# LCD1602_Driver.net
KiCad netlist of a schematic drawn in Altium Designer
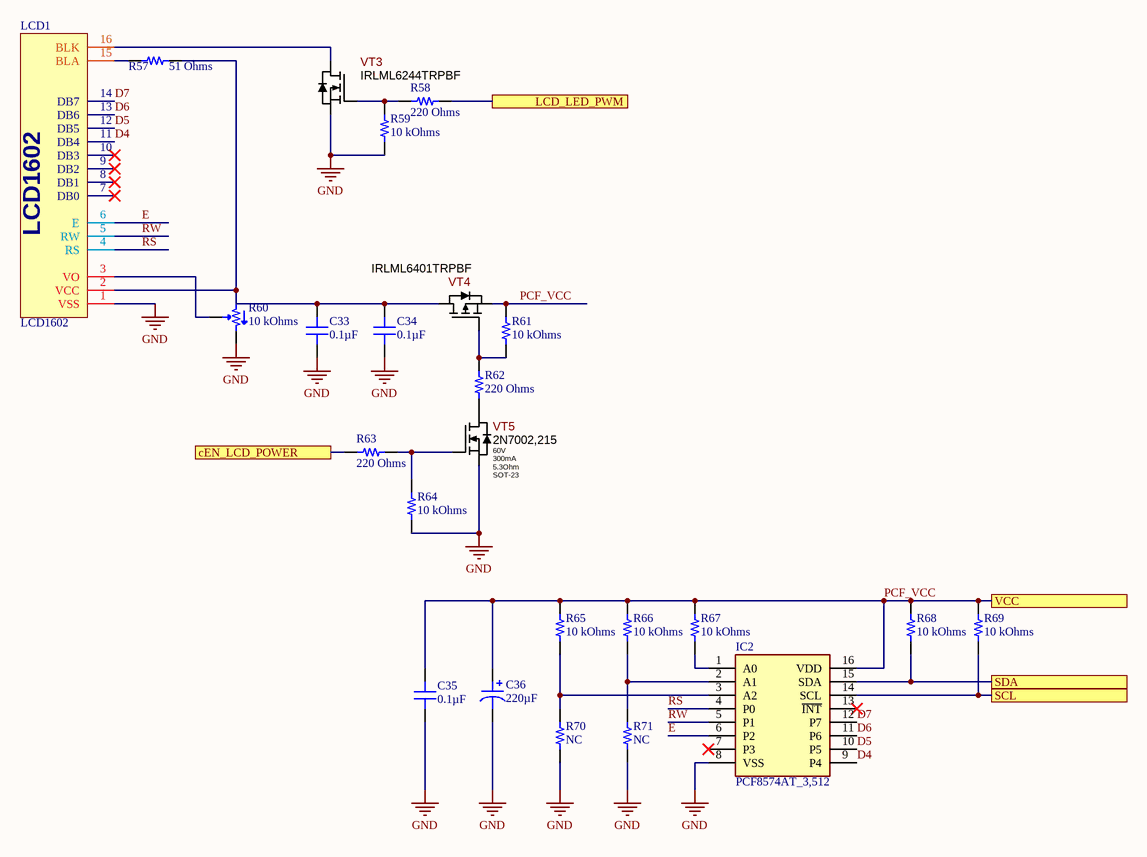
[diagram p0: LCD1602_Driver.SchDoc]

(export (version "E")
  (design (tool "Eeschema 10.0.6"))
  (components
    (comp (ref "C33")
      (value "0.1µF")
      (footprint "CAP 0805_2012")
      (description "CAP CER 0.1UF 50V X7R 0805")
      (fields (field (name "PART NUMBER") "CC0805MRX7R9BB104") (field (name "MANUFACTURER") "Yageo"))
      (libsource (lib "Celestial Altium Library - altium_library") (part "Capacitor"))
    )
    (comp (ref "C34")
      (value "0.1µF")
      (footprint "CAP 0805_2012")
      (description "CAP CER 0.1UF 50V X7R 0805")
      (fields (field (name "PART NUMBER") "CC0805MRX7R9BB104") (field (name "MANUFACTURER") "Yageo"))
      (libsource (lib "Celestial Altium Library - altium_library") (part "Capacitor"))
    )
    (comp (ref "C35")
      (value "0.1µF")
      (footprint "CAP 0805_2012")
      (description "CAP CER 0.1UF 50V X7R 0805")
      (fields (field (name "PART NUMBER") "CC0805MRX7R9BB104") (field (name "MANUFACTURER") "Yageo"))
      (libsource (lib "Celestial Altium Library - altium_library") (part "Capacitor"))
    )
    (comp (ref "C36")
      (value "220µF")
      (footprint "CAP ALSMD POLY 5.3MM H6.0MM")
      (description "CAP ALUM POLY 220UF 20% 6.3V SMD")
      (fields
        (field (name "PART NUMBER") "6SVPE220MW")
        (field (name "MANUFACTURER") "Panasonic Electronic Components")
      )
      (libsource (lib "Celestial Altium Library - altium_library") (part "Polarised Capacitor"))
    )
    (comp (ref "IC2")
      (value "PCF8574AT_3,512")
      (footprint "SamacSys:SOIC127P1032X265-16N")
      (description "Integrated Circuit")
      (fields
        (field (name "MANUFACTURER_PART_NUMBER") "PCF8574AT/3,512")
        (field (name "MOUSER PART NUMBER") "771-PCF85AT3512")
      )
      (libsource (lib "*") (part "PCF8574AT_3,512"))
    )
    (comp (ref "LCD1")
      (value "LCD1602")
      (footprint "LCD1602")
      (libsource (lib "Miscellaneous LCD") (part "LCD1602"))
    )
    (comp (ref "R57")
      (value "51 Ohms")
      (footprint "RES 0805_2012")
      (description "RES SMD 51 OHM 1% 1/4W 0805")
      (fields (field (name "PART NUMBER") "CRM0805-FX-51R0ELF") (field (name "MANUFACTURER") "Bourns Inc."))
      (libsource (lib "Celestial Altium Library - altium_library") (part "Resistor"))
    )
    (comp (ref "R58")
      (value "220 Ohms")
      (footprint "RES 0805_2012")
      (description "CRGP 0805 220R 1%")
      (fields
        (field (name "PART NUMBER") "CRGP0805F220R")
        (field (name "MANUFACTURER") "TE Connectivity Passive Product")
      )
      (libsource (lib "Celestial Altium Library - altium_library") (part "Resistor"))
    )
    (comp (ref "R59")
      (value "10 kOhms")
      (footprint "RES 0805_2012")
      (description "RES 10K OHM 0.1% 1/10W 0805")
      (fields
        (field (name "PART NUMBER") "RNCS0805BKE10K0")
        (field (name "MANUFACTURER") "Stackpole Electronics Inc")
      )
      (libsource (lib "Celestial Altium Library - altium_library") (part "Resistor"))
    )
    (comp (ref "R60")
      (value "10 kOhms")
      (footprint "POT BOURNS TRIMPOT TC33")
      (description "TRIMMER 10K OHM 0.1W J LEAD TOP")
      (fields (field (name "PART NUMBER") "TC33X-2-103E") (field (name "MANUFACTURER") "Bourns Inc."))
      (libsource (lib "Celestial Altium Library - altium_library") (part "Potentiometer"))
    )
    (comp (ref "R61")
      (value "10 kOhms")
      (footprint "RES 0805_2012")
      (description "RES 10K OHM 0.1% 1/10W 0805")
      (fields
        (field (name "PART NUMBER") "RNCS0805BKE10K0")
        (field (name "MANUFACTURER") "Stackpole Electronics Inc")
      )
      (libsource (lib "Celestial Altium Library - altium_library") (part "Resistor"))
    )
    (comp (ref "R62")
      (value "220 Ohms")
      (footprint "RES 0805_2012")
      (description "CRGP 0805 220R 1%")
      (fields
        (field (name "PART NUMBER") "CRGP0805F220R")
        (field (name "MANUFACTURER") "TE Connectivity Passive Product")
      )
      (libsource (lib "Celestial Altium Library - altium_library") (part "Resistor"))
    )
    (comp (ref "R63")
      (value "220 Ohms")
      (footprint "RES 0805_2012")
      (description "CRGP 0805 220R 1%")
      (fields
        (field (name "PART NUMBER") "CRGP0805F220R")
        (field (name "MANUFACTURER") "TE Connectivity Passive Product")
      )
      (libsource (lib "Celestial Altium Library - altium_library") (part "Resistor"))
    )
    (comp (ref "R64")
      (value "10 kOhms")
      (footprint "RES 0805_2012")
      (description "RES 10K OHM 0.1% 1/10W 0805")
      (fields
        (field (name "PART NUMBER") "RNCS0805BKE10K0")
        (field (name "MANUFACTURER") "Stackpole Electronics Inc")
      )
      (libsource (lib "Celestial Altium Library - altium_library") (part "Resistor"))
    )
    (comp (ref "R65")
      (value "10 kOhms")
      (footprint "RES 0805_2012")
      (description "RES 10K OHM 0.1% 1/10W 0805")
      (fields
        (field (name "PART NUMBER") "RNCS0805BKE10K0")
        (field (name "MANUFACTURER") "Stackpole Electronics Inc")
      )
      (libsource (lib "Celestial Altium Library - altium_library") (part "Resistor"))
    )
    (comp (ref "R66")
      (value "10 kOhms")
      (footprint "RES 0805_2012")
      (description "RES 10K OHM 0.1% 1/10W 0805")
      (fields
        (field (name "PART NUMBER") "RNCS0805BKE10K0")
        (field (name "MANUFACTURER") "Stackpole Electronics Inc")
      )
      (libsource (lib "Celestial Altium Library - altium_library") (part "Resistor"))
    )
    (comp (ref "R67")
      (value "10 kOhms")
      (footprint "RES 0805_2012")
      (description "RES 10K OHM 0.1% 1/10W 0805")
      (fields
        (field (name "PART NUMBER") "RNCS0805BKE10K0")
        (field (name "MANUFACTURER") "Stackpole Electronics Inc")
      )
      (libsource (lib "Celestial Altium Library - altium_library") (part "Resistor"))
    )
    (comp (ref "R68")
      (value "10 kOhms")
      (footprint "RES 0805_2012")
      (description "RES 10K OHM 0.1% 1/10W 0805")
      (fields
        (field (name "PART NUMBER") "RNCS0805BKE10K0")
        (field (name "MANUFACTURER") "Stackpole Electronics Inc")
      )
      (libsource (lib "Celestial Altium Library - altium_library") (part "Resistor"))
    )
    (comp (ref "R69")
      (value "10 kOhms")
      (footprint "RES 0805_2012")
      (description "RES 10K OHM 0.1% 1/10W 0805")
      (fields
        (field (name "PART NUMBER") "RNCS0805BKE10K0")
        (field (name "MANUFACTURER") "Stackpole Electronics Inc")
      )
      (libsource (lib "Celestial Altium Library - altium_library") (part "Resistor"))
    )
    (comp (ref "R70")
      (value "NC")
      (footprint "RES 0805_2012")
      (description "RES 10K OHM 0.1% 1/10W 0805")
      (fields
        (field (name "PART NUMBER") "RNCS0805BKE10K0")
        (field (name "MANUFACTURER") "Stackpole Electronics Inc")
      )
      (libsource (lib "Celestial Altium Library - altium_library") (part "Resistor"))
    )
    (comp (ref "R71")
      (value "NC")
      (footprint "RES 0805_2012")
      (description "RES 10K OHM 0.1% 1/10W 0805")
      (fields
        (field (name "PART NUMBER") "RNCS0805BKE10K0")
        (field (name "MANUFACTURER") "Stackpole Electronics Inc")
      )
      (libsource (lib "Celestial Altium Library - altium_library") (part "Resistor"))
    )
    (comp (ref "VT3")
      (value "IRLML6244")
      (footprint "SOT-23_MED")
      (description "20V, 6.3A max N-Channel HEXFET MOSFET, 21mOhm @ Vgs = 4.5V")
      (fields
        (field (name "PART NUMBER") "IRLML6244TRPBF")
        (field (name "MANUFACTURER") "Infineon Technologies")
      )
      (libsource (lib "Transistors") (part "IRLML6244TRPBF"))
    )
    (comp (ref "VT4")
      (value "IRLML6401")
      (footprint "SOT-23_MED")
      (description "-12V, -4.3A max P-Channel HEXFET MOSFET, 50mOhm @ Vgs = -4.5V")
      (fields
        (field (name "PART NUMBER") "IRLML6401TRPBF")
        (field (name "MANUFACTURER") "Infineon Technologies")
      )
      (libsource (lib "Transistors") (part "IRLML6401TRPBF"))
    )
    (comp (ref "VT5")
      (value "2N7002")
      (footprint "SOT-23_MED")
      (description "60V, 300mA max N-Channel Trench MOSFET, 3.8Ohm @ Vgs = 4.5V")
      (fields
        (field (name "MANUFACTURER") "Nexperia USA Inc.")
        (field (name "PART NUMBER") "2N7002,215")
        (field (name "VDS") "60V")
        (field (name "ID") "300mA")
        (field (name "RDS") "5.3Ohm")
        (field (name "PACKAGE") "SOT-23")
      )
      (libsource (lib "Transistors") (part "2N7002,215"))
    )
  )
  (nets
    (net (code "1") (name "/D4") (class "Default")
      (node (ref "IC2") (pin "9") (pinfunction "P4_9") (pintype "passive"))
      (node (ref "LCD1") (pin "11") (pinfunction "DB4_11") (pintype "passive"))
    )
    (net (code "2") (name "/D5") (class "Default")
      (node (ref "IC2") (pin "10") (pinfunction "P5_10") (pintype "passive"))
      (node (ref "LCD1") (pin "12") (pinfunction "DB5_12") (pintype "passive"))
    )
    (net (code "3") (name "/D6") (class "Default")
      (node (ref "IC2") (pin "11") (pinfunction "P6_11") (pintype "passive"))
      (node (ref "LCD1") (pin "13") (pinfunction "DB6_13") (pintype "passive"))
    )
    (net (code "4") (name "/D7") (class "Default")
      (node (ref "IC2") (pin "12") (pinfunction "P7_12") (pintype "passive"))
      (node (ref "LCD1") (pin "14") (pinfunction "DB7_14") (pintype "passive"))
    )
    (net (code "5") (name "/E") (class "Default")
      (node (ref "IC2") (pin "6") (pinfunction "P2_6") (pintype "passive"))
      (node (ref "LCD1") (pin "6") (pinfunction "E_6") (pintype "passive"))
    )
    (net (code "6") (name "/LCD_LED_PWM") (class "Default")
      (node (ref "R58") (pin "1") (pinfunction "1_1") (pintype "passive"))
    )
    (net (code "7") (name "/PCF_VCC") (class "Default")
      (node (ref "C35") (pin "2") (pinfunction "2_2") (pintype "passive"))
      (node (ref "C36") (pin "1") (pinfunction "1_1") (pintype "passive"))
      (node (ref "IC2") (pin "16") (pinfunction "VDD_16") (pintype "passive"))
      (node (ref "R61") (pin "2") (pinfunction "2_2") (pintype "passive"))
      (node (ref "R65") (pin "2") (pinfunction "2_2") (pintype "passive"))
      (node (ref "R66") (pin "2") (pinfunction "2_2") (pintype "passive"))
      (node (ref "R67") (pin "1") (pinfunction "1_1") (pintype "passive"))
      (node (ref "R68") (pin "2") (pinfunction "2_2") (pintype "passive"))
      (node (ref "R69") (pin "1") (pinfunction "1_1") (pintype "passive"))
      (node (ref "VT4") (pin "2") (pinfunction "S_2") (pintype "passive"))
    )
    (net (code "8") (name "/RS") (class "Default")
      (node (ref "IC2") (pin "4") (pinfunction "P0_4") (pintype "passive"))
      (node (ref "LCD1") (pin "4") (pinfunction "RS_4") (pintype "passive"))
    )
    (net (code "9") (name "/RW") (class "Default")
      (node (ref "IC2") (pin "5") (pinfunction "P1_5") (pintype "passive"))
      (node (ref "LCD1") (pin "5") (pinfunction "RW_5") (pintype "passive"))
    )
    (net (code "10") (name "/SCL") (class "Default")
      (node (ref "IC2") (pin "14") (pinfunction "SCL_14") (pintype "passive"))
      (node (ref "R69") (pin "2") (pinfunction "2_2") (pintype "passive"))
    )
    (net (code "11") (name "/SDA") (class "Default")
      (node (ref "IC2") (pin "15") (pinfunction "SDA_15") (pintype "passive"))
      (node (ref "R68") (pin "1") (pinfunction "1_1") (pintype "passive"))
    )
    (net (code "12") (name "/cEN_LCD_POWER") (class "Default")
      (node (ref "R63") (pin "2") (pinfunction "2_2") (pintype "passive"))
    )
    (net (code "13") (name "GND") (class "Default")
      (node (ref "C33") (pin "1") (pinfunction "1_1") (pintype "passive"))
      (node (ref "C34") (pin "1") (pinfunction "1_1") (pintype "passive"))
      (node (ref "C35") (pin "1") (pinfunction "1_1") (pintype "passive"))
      (node (ref "C36") (pin "2") (pinfunction "2_2") (pintype "passive"))
      (node (ref "IC2") (pin "8") (pinfunction "VSS_8") (pintype "passive"))
      (node (ref "LCD1") (pin "1") (pinfunction "VSS_1") (pintype "passive"))
      (node (ref "R59") (pin "1") (pinfunction "1_1") (pintype "passive"))
      (node (ref "R60") (pin "3") (pinfunction "3_3") (pintype "passive"))
      (node (ref "R64") (pin "1") (pinfunction "1_1") (pintype "passive"))
      (node (ref "R70") (pin "1") (pinfunction "1_1") (pintype "passive"))
      (node (ref "R71") (pin "1") (pinfunction "1_1") (pintype "passive"))
      (node (ref "VT3") (pin "2") (pinfunction "S_2") (pintype "passive"))
      (node (ref "VT5") (pin "2") (pinfunction "S_2") (pintype "passive"))
    )
    (net (code "14") (name "Net-(IC2-A0)") (class "Default")
      (node (ref "IC2") (pin "1") (pinfunction "A0_1") (pintype "passive"))
      (node (ref "R67") (pin "2") (pinfunction "2_2") (pintype "passive"))
    )
    (net (code "15") (name "Net-(IC2-A1)") (class "Default")
      (node (ref "IC2") (pin "2") (pinfunction "A1_2") (pintype "passive"))
      (node (ref "R66") (pin "1") (pinfunction "1_1") (pintype "passive"))
      (node (ref "R71") (pin "2") (pinfunction "2_2") (pintype "passive"))
    )
    (net (code "16") (name "Net-(IC2-A2)") (class "Default")
      (node (ref "IC2") (pin "3") (pinfunction "A2_3") (pintype "passive"))
      (node (ref "R65") (pin "1") (pinfunction "1_1") (pintype "passive"))
      (node (ref "R70") (pin "2") (pinfunction "2_2") (pintype "passive"))
    )
    (net (code "17") (name "Net-(LCD1-BLA)") (class "Default")
      (node (ref "LCD1") (pin "15") (pinfunction "BLA_15") (pintype "passive"))
      (node (ref "R57") (pin "1") (pinfunction "1_1") (pintype "passive"))
    )
    (net (code "18") (name "Net-(LCD1-BLK)") (class "Default")
      (node (ref "LCD1") (pin "16") (pinfunction "BLK_16") (pintype "passive"))
      (node (ref "VT3") (pin "3") (pinfunction "D_3") (pintype "passive"))
    )
    (net (code "19") (name "Net-(LCD1-VCC)") (class "Default")
      (node (ref "C33") (pin "2") (pinfunction "2_2") (pintype "passive"))
      (node (ref "C34") (pin "2") (pinfunction "2_2") (pintype "passive"))
      (node (ref "LCD1") (pin "2") (pinfunction "VCC_2") (pintype "passive"))
      (node (ref "R57") (pin "2") (pinfunction "2_2") (pintype "passive"))
      (node (ref "R60") (pin "1") (pinfunction "1_1") (pintype "passive"))
      (node (ref "VT4") (pin "3") (pinfunction "D_3") (pintype "passive"))
    )
    (net (code "20") (name "Net-(LCD1-VO)") (class "Default")
      (node (ref "LCD1") (pin "3") (pinfunction "VO_3") (pintype "passive"))
      (node (ref "R60") (pin "2") (pinfunction "2_2") (pintype "passive"))
    )
    (net (code "21") (name "Net-(VT3-G)") (class "Default")
      (node (ref "R58") (pin "2") (pinfunction "2_2") (pintype "passive"))
      (node (ref "R59") (pin "2") (pinfunction "2_2") (pintype "passive"))
      (node (ref "VT3") (pin "1") (pinfunction "G_1") (pintype "passive"))
    )
    (net (code "22") (name "Net-(VT4-G)") (class "Default")
      (node (ref "R61") (pin "1") (pinfunction "1_1") (pintype "passive"))
      (node (ref "R62") (pin "2") (pinfunction "2_2") (pintype "passive"))
      (node (ref "VT4") (pin "1") (pinfunction "G_1") (pintype "passive"))
    )
    (net (code "23") (name "Net-(VT5-D)") (class "Default")
      (node (ref "R62") (pin "1") (pinfunction "1_1") (pintype "passive"))
      (node (ref "VT5") (pin "3") (pinfunction "D_3") (pintype "passive"))
    )
    (net (code "24") (name "Net-(VT5-G)") (class "Default")
      (node (ref "R63") (pin "1") (pinfunction "1_1") (pintype "passive"))
      (node (ref "R64") (pin "2") (pinfunction "2_2") (pintype "passive"))
      (node (ref "VT5") (pin "1") (pinfunction "G_1") (pintype "passive"))
    )
    (net (code "25") (name "unconnected-(IC2-P3-Pad7)") (class "Default")
      (node (ref "IC2") (pin "7") (pinfunction "P3_7") (pintype "passive+no_connect"))
    )
    (net (code "26") (name "unconnected-(IC2-~{INT}-Pad13)") (class "Default")
      (node (ref "IC2") (pin "13") (pinfunction "~{INT}_13") (pintype "passive+no_connect"))
    )
    (net (code "27") (name "unconnected-(LCD1-DB0-Pad7)") (class "Default")
      (node (ref "LCD1") (pin "7") (pinfunction "DB0_7") (pintype "passive+no_connect"))
    )
    (net (code "28") (name "unconnected-(LCD1-DB1-Pad8)") (class "Default")
      (node (ref "LCD1") (pin "8") (pinfunction "DB1_8") (pintype "passive+no_connect"))
    )
    (net (code "29") (name "unconnected-(LCD1-DB2-Pad9)") (class "Default")
      (node (ref "LCD1") (pin "9") (pinfunction "DB2_9") (pintype "passive+no_connect"))
    )
    (net (code "30") (name "unconnected-(LCD1-DB3-Pad10)") (class "Default")
      (node (ref "LCD1") (pin "10") (pinfunction "DB3_10") (pintype "passive+no_connect"))
    )
  )
)
